# Led_rgb.net
KiCad netlist of a schematic drawn in Altium Designer
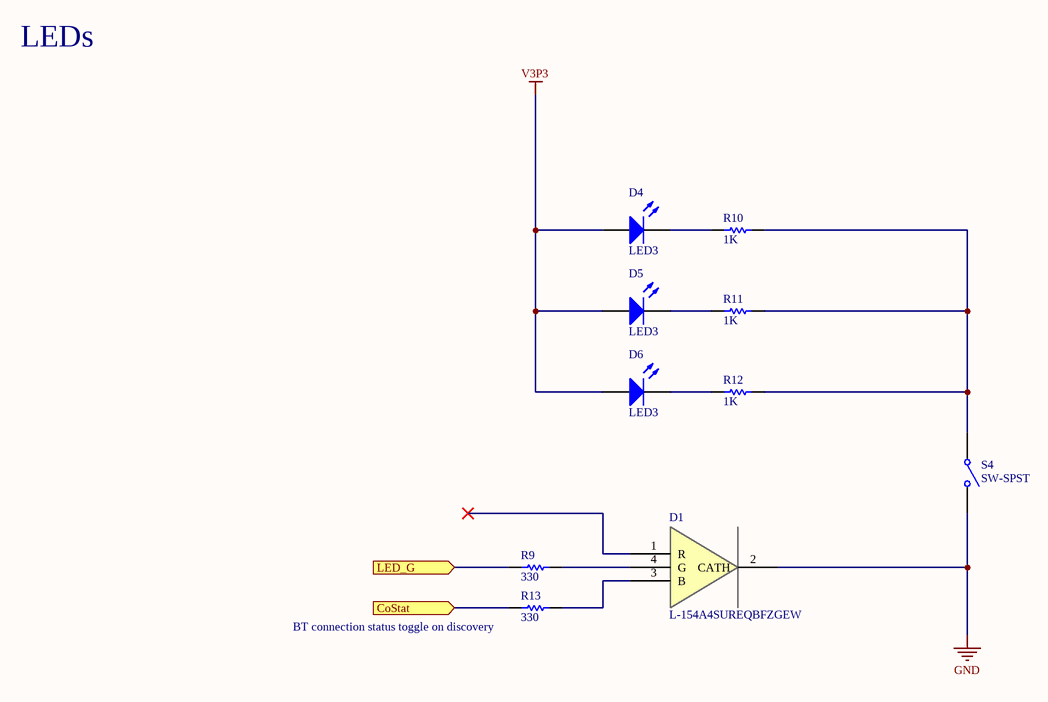
[diagram p0: Led_rgb.SchDoc]

(export (version "E")
  (design (tool "Eeschema 10.0.6"))
  (components
    (comp (ref "D1")
      (value "L-154A4SUREQBFZGEW")
      (footprint "L-154A4SUREQBFZGEW")
      (description "LED RGB")
      (libsource (lib "Schlib") (part "L-154A4SUREQBFZGEW"))
    )
    (comp (ref "D4")
      (value "LED3")
      (footprint "LED2.5")
      (description "Typical BLUE SiC LED")
      (libsource (lib "Miscellaneous Devices") (part "LED3"))
    )
    (comp (ref "D5")
      (value "LED3")
      (footprint "LED2.5")
      (description "Typical BLUE SiC LED")
      (libsource (lib "Miscellaneous Devices") (part "LED3"))
    )
    (comp (ref "D6")
      (value "LED3")
      (footprint "LED2.5")
      (description "Typical BLUE SiC LED")
      (libsource (lib "Miscellaneous Devices") (part "LED3"))
    )
    (comp (ref "R9")
      (value "330")
      (footprint "own_0603")
      (description "Resistor")
      (fields (field (name "PUBLISHER") "Altium Limited"))
      (libsource (lib "Miscellaneous Devices") (part "Res1"))
    )
    (comp (ref "R10")
      (value "1K")
      (footprint "own_0603")
      (description "Resistor")
      (fields (field (name "PUBLISHER") "Altium Limited"))
      (libsource (lib "Miscellaneous Devices") (part "Res1"))
    )
    (comp (ref "R11")
      (value "1K")
      (footprint "own_0603")
      (description "Resistor")
      (fields (field (name "PUBLISHER") "Altium Limited"))
      (libsource (lib "Miscellaneous Devices") (part "Res1"))
    )
    (comp (ref "R12")
      (value "1K")
      (footprint "own_0603")
      (description "Resistor")
      (fields (field (name "PUBLISHER") "Altium Limited"))
      (libsource (lib "Miscellaneous Devices") (part "Res1"))
    )
    (comp (ref "R13")
      (value "330")
      (footprint "own_0603")
      (description "Resistor")
      (fields (field (name "PUBLISHER") "Altium Limited"))
      (libsource (lib "Miscellaneous Devices") (part "Res1"))
    )
    (comp (ref "S4")
      (value "SW-SPST")
      (footprint "SPST-2")
      (description "Single-Pole, Single-Throw Switch")
      (libsource (lib "Miscellaneous Devices") (part "SW-SPST"))
    )
  )
  (nets
    (net (code "1") (name "/CoStat") (class "Default")
      (node (ref "R13") (pin "2") (pinfunction "2_2") (pintype "passive"))
    )
    (net (code "2") (name "/LED_G") (class "Default")
      (node (ref "R9") (pin "2") (pinfunction "2_2") (pintype "passive"))
    )
    (net (code "3") (name "GND") (class "Default")
      (node (ref "D1") (pin "2") (pinfunction "CATH_2") (pintype "passive"))
      (node (ref "S4") (pin "2") (pinfunction "NO_2") (pintype "passive"))
    )
    (net (code "4") (name "Net-(D1-B)") (class "Default")
      (node (ref "D1") (pin "3") (pinfunction "B_3") (pintype "passive"))
      (node (ref "R13") (pin "1") (pinfunction "1_1") (pintype "passive"))
    )
    (net (code "5") (name "Net-(D1-G)") (class "Default")
      (node (ref "D1") (pin "4") (pinfunction "G_4") (pintype "passive"))
      (node (ref "R9") (pin "1") (pinfunction "1_1") (pintype "passive"))
    )
    (net (code "6") (name "Net-(D4-K)") (class "Default")
      (node (ref "D4") (pin "2") (pinfunction "K_2") (pintype "passive"))
      (node (ref "R10") (pin "1") (pinfunction "1_1") (pintype "passive"))
    )
    (net (code "7") (name "Net-(D5-K)") (class "Default")
      (node (ref "D5") (pin "2") (pinfunction "K_2") (pintype "passive"))
      (node (ref "R11") (pin "1") (pinfunction "1_1") (pintype "passive"))
    )
    (net (code "8") (name "Net-(D6-K)") (class "Default")
      (node (ref "D6") (pin "2") (pinfunction "K_2") (pintype "passive"))
      (node (ref "R12") (pin "1") (pinfunction "1_1") (pintype "passive"))
    )
    (net (code "9") (name "Net-(S4-COMMON)") (class "Default")
      (node (ref "R10") (pin "2") (pinfunction "2_2") (pintype "passive"))
      (node (ref "R11") (pin "2") (pinfunction "2_2") (pintype "passive"))
      (node (ref "R12") (pin "2") (pinfunction "2_2") (pintype "passive"))
      (node (ref "S4") (pin "1") (pinfunction "COMMON_1") (pintype "passive"))
    )
    (net (code "10") (name "V3P3") (class "Default")
      (node (ref "D4") (pin "1") (pinfunction "A_1") (pintype "passive"))
      (node (ref "D5") (pin "1") (pinfunction "A_1") (pintype "passive"))
      (node (ref "D6") (pin "1") (pinfunction "A_1") (pintype "passive"))
    )
    (net (code "11") (name "unconnected-(D1-R-Pad1)") (class "Default")
      (node (ref "D1") (pin "1") (pinfunction "R_1") (pintype "passive+no_connect"))
    )
  )
)
